# 14DoF_MPU9150.net
KiCad netlist of a schematic drawn in EAGLE
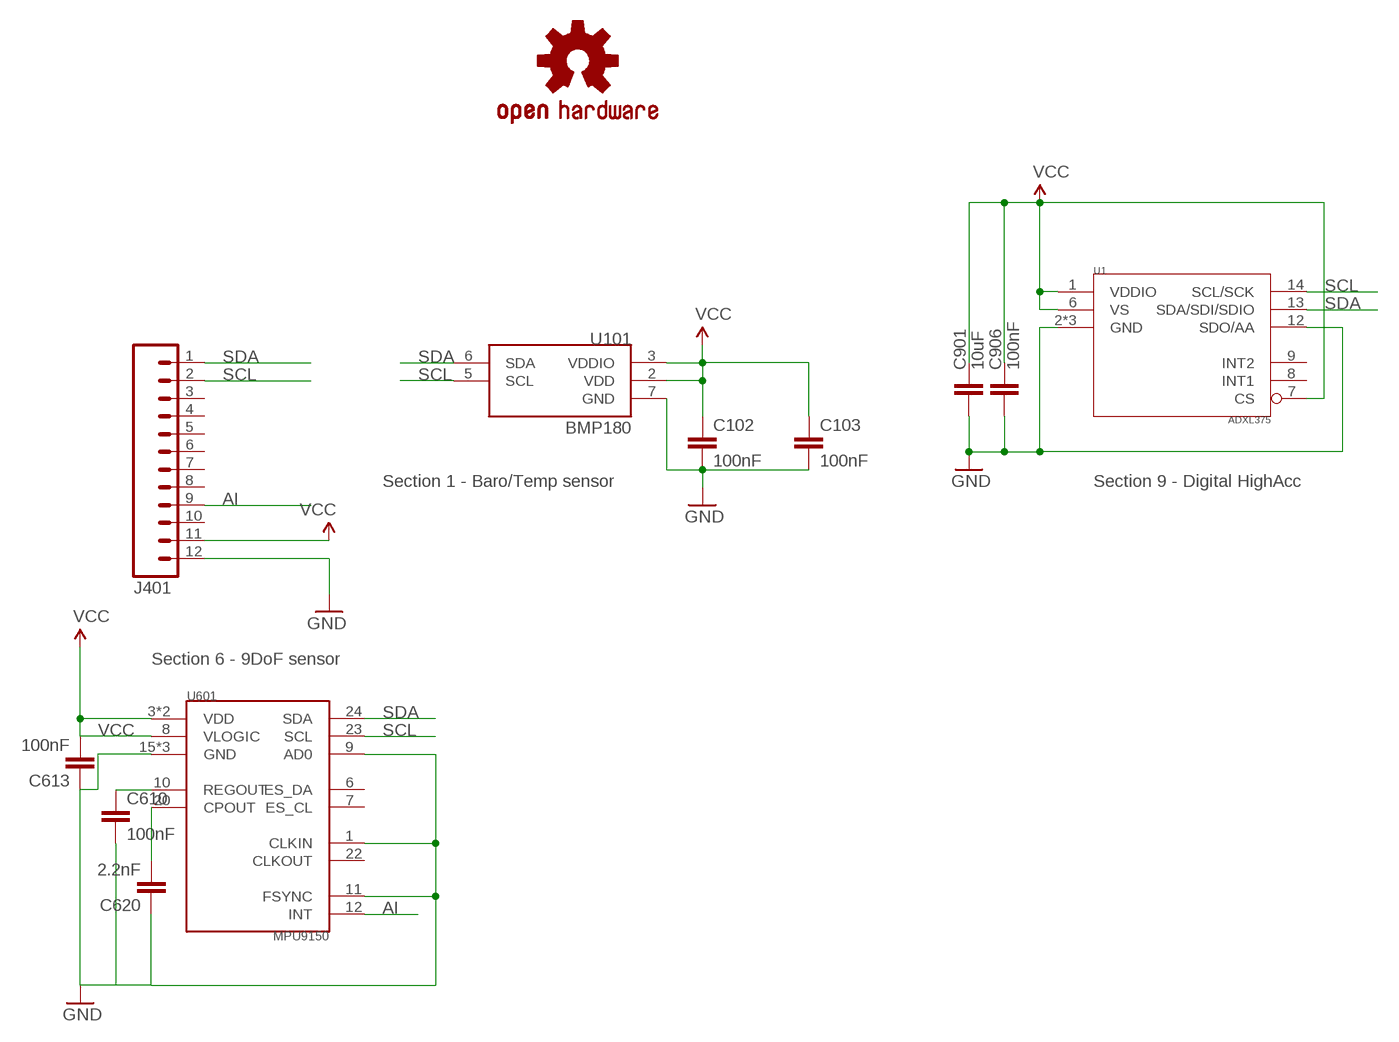
[diagram p0: schematic, sheet 1]

(export (version "E")
  (design (tool "Eeschema 10.0.6"))
  (components
    (comp (ref "C102")
      (value "100nF")
      (footprint "eagle-import:0603-CAP")
      (libsource (lib "eagle-import") (part "CAP0603-CAP"))
    )
    (comp (ref "C103")
      (value "100nF")
      (footprint "eagle-import:0603-CAP")
      (libsource (lib "eagle-import") (part "CAP0603-CAP"))
    )
    (comp (ref "C610")
      (value "100nF")
      (footprint "eagle-import:0603-CAP")
      (libsource (lib "eagle-import") (part "CAP0603-CAP"))
    )
    (comp (ref "C613")
      (value "100nF")
      (footprint "eagle-import:0603-CAP")
      (libsource (lib "eagle-import") (part "CAP0603-CAP"))
    )
    (comp (ref "C620")
      (value "2.2nF")
      (footprint "eagle-import:0603-CAP")
      (libsource (lib "eagle-import") (part "CAP0603-CAP"))
    )
    (comp (ref "C901")
      (value "10uF")
      (footprint "eagle-import:0603-CAP")
      (libsource (lib "eagle-import") (part "CAP0603-CAP"))
    )
    (comp (ref "C906")
      (value "100nF")
      (footprint "eagle-import:0402-CAP")
      (libsource (lib "eagle-import") (part "SparkFun-Passives_CAP0402-CAP"))
    )
    (comp (ref "J401")
      (value "M12PTH")
      (footprint "eagle-import:1X12")
      (libsource (lib "eagle-import") (part "M12PTH"))
    )
    (comp (ref "U$2")
      (value "OSHW-LOGOS")
      (footprint "eagle-import:OSHW-LOGO-S")
      (libsource (lib "eagle-import") (part "OSHW-LOGOS"))
    )
    (comp (ref "U1")
      (value "ADXL375")
      (footprint "eagle-import:ADXL375")
      (libsource (lib "eagle-import") (part "ADXL375"))
    )
    (comp (ref "U101")
      (value "BMP180")
      (footprint "eagle-import:BMP180")
      (libsource (lib "eagle-import") (part "BMP180"))
    )
    (comp (ref "U601")
      (value "MPU9150")
      (footprint "eagle-import:LLGA24")
      (libsource (lib "eagle-import") (part "MPU9150"))
    )
  )
  (nets
    (net (code "1") (name "/AI") (class "Default")
      (node (ref "J401") (pin "9") (pinfunction "9_9") (pintype "passive"))
      (node (ref "U601") (pin "12") (pinfunction "INT_12") (pintype "bidirectional"))
    )
    (net (code "2") (name "/SCL") (class "Default")
      (node (ref "J401") (pin "2") (pinfunction "2_2") (pintype "passive"))
      (node (ref "U1") (pin "14") (pinfunction "SCL/SCK_14") (pintype "input"))
      (node (ref "U101") (pin "5") (pinfunction "SCL_5") (pintype "input"))
      (node (ref "U601") (pin "23") (pinfunction "SCL_23") (pintype "bidirectional"))
    )
    (net (code "3") (name "/SDA") (class "Default")
      (node (ref "J401") (pin "1") (pinfunction "1_1") (pintype "passive"))
      (node (ref "U1") (pin "13") (pinfunction "SDA/SDI/SDIO_13") (pintype "bidirectional"))
      (node (ref "U101") (pin "6") (pinfunction "SDA_6") (pintype "bidirectional"))
      (node (ref "U601") (pin "24") (pinfunction "SDA_24") (pintype "bidirectional"))
    )
    (net (code "4") (name "GND") (class "Default")
      (node (ref "C102") (pin "2") (pinfunction "2_2") (pintype "passive"))
      (node (ref "C103") (pin "2") (pinfunction "2_2") (pintype "passive"))
      (node (ref "C610") (pin "2") (pinfunction "2_2") (pintype "passive"))
      (node (ref "C613") (pin "1") (pinfunction "1_1") (pintype "passive"))
      (node (ref "C620") (pin "1") (pinfunction "1_1") (pintype "passive"))
      (node (ref "C901") (pin "2") (pinfunction "2_2") (pintype "passive"))
      (node (ref "C906") (pin "2") (pinfunction "2_2") (pintype "passive"))
      (node (ref "J401") (pin "12") (pinfunction "12_12") (pintype "passive"))
      (node (ref "U1") (pin "12") (pinfunction "SDO/AA_12") (pintype "bidirectional"))
      (node (ref "U1") (pin "2") (pinfunction "GND_2") (pintype "power_in"))
      (node (ref "U1") (pin "4") (pinfunction "GND_4") (pintype "power_in"))
      (node (ref "U1") (pin "5") (pinfunction "GND_5") (pintype "power_in"))
      (node (ref "U101") (pin "7") (pinfunction "GND_7") (pintype "power_in"))
      (node (ref "U601") (pin "1") (pinfunction "CLKIN_1") (pintype "bidirectional"))
      (node (ref "U601") (pin "11") (pinfunction "FSYNC_11") (pintype "bidirectional"))
      (node (ref "U601") (pin "15") (pinfunction "GND_15") (pintype "bidirectional"))
      (node (ref "U601") (pin "17") (pinfunction "GND_17") (pintype "bidirectional"))
      (node (ref "U601") (pin "18") (pinfunction "GND_18") (pintype "bidirectional"))
      (node (ref "U601") (pin "9") (pinfunction "AD0_9") (pintype "bidirectional"))
    )
    (net (code "5") (name "Net-(U601-CPOUT)") (class "Default")
      (node (ref "C620") (pin "2") (pinfunction "2_2") (pintype "passive"))
      (node (ref "U601") (pin "20") (pinfunction "CPOUT_20") (pintype "bidirectional"))
    )
    (net (code "6") (name "Net-(U601-REGOUT)") (class "Default")
      (node (ref "C610") (pin "1") (pinfunction "1_1") (pintype "passive"))
      (node (ref "U601") (pin "10") (pinfunction "REGOUT_10") (pintype "bidirectional"))
    )
    (net (code "7") (name "VCC") (class "Default")
      (node (ref "C102") (pin "1") (pinfunction "1_1") (pintype "passive"))
      (node (ref "C103") (pin "1") (pinfunction "1_1") (pintype "passive"))
      (node (ref "C613") (pin "2") (pinfunction "2_2") (pintype "passive"))
      (node (ref "C901") (pin "1") (pinfunction "1_1") (pintype "passive"))
      (node (ref "C906") (pin "1") (pinfunction "1_1") (pintype "passive"))
      (node (ref "J401") (pin "11") (pinfunction "11_11") (pintype "passive"))
      (node (ref "U1") (pin "1") (pinfunction "VDDIO_1") (pintype "power_in"))
      (node (ref "U1") (pin "6") (pinfunction "VS_6") (pintype "power_in"))
      (node (ref "U1") (pin "7") (pinfunction "CS_7") (pintype "input"))
      (node (ref "U101") (pin "2") (pinfunction "VDD_2") (pintype "power_in"))
      (node (ref "U101") (pin "3") (pinfunction "VDDIO_3") (pintype "power_in"))
      (node (ref "U601") (pin "13") (pinfunction "VDD_13") (pintype "bidirectional"))
      (node (ref "U601") (pin "3") (pinfunction "VDD_3") (pintype "bidirectional"))
      (node (ref "U601") (pin "8") (pinfunction "VLOGIC_8") (pintype "bidirectional"))
    )
    (net (code "8") (name "unconnected-(J401-Pad3)") (class "Default")
      (node (ref "J401") (pin "3") (pinfunction "3_3") (pintype "passive"))
    )
    (net (code "9") (name "unconnected-(J401-Pad4)") (class "Default")
      (node (ref "J401") (pin "4") (pinfunction "4_4") (pintype "passive"))
    )
    (net (code "10") (name "unconnected-(J401-Pad5)") (class "Default")
      (node (ref "J401") (pin "5") (pinfunction "5_5") (pintype "passive"))
    )
    (net (code "11") (name "unconnected-(J401-Pad6)") (class "Default")
      (node (ref "J401") (pin "6") (pinfunction "6_6") (pintype "passive"))
    )
    (net (code "12") (name "unconnected-(J401-Pad7)") (class "Default")
      (node (ref "J401") (pin "7") (pinfunction "7_7") (pintype "passive"))
    )
    (net (code "13") (name "unconnected-(J401-Pad8)") (class "Default")
      (node (ref "J401") (pin "8") (pinfunction "8_8") (pintype "passive"))
    )
    (net (code "14") (name "unconnected-(J401-Pad10)") (class "Default")
      (node (ref "J401") (pin "10") (pinfunction "10_10") (pintype "passive"))
    )
    (net (code "15") (name "unconnected-(U1-INT1-Pad8)") (class "Default")
      (node (ref "U1") (pin "8") (pinfunction "INT1_8") (pintype "output"))
    )
    (net (code "16") (name "unconnected-(U1-INT2-Pad9)") (class "Default")
      (node (ref "U1") (pin "9") (pinfunction "INT2_9") (pintype "output"))
    )
    (net (code "17") (name "unconnected-(U601-CLKOUT-Pad22)") (class "Default")
      (node (ref "U601") (pin "22") (pinfunction "CLKOUT_22") (pintype "bidirectional"))
    )
    (net (code "18") (name "unconnected-(U601-ES_CL-Pad7)") (class "Default")
      (node (ref "U601") (pin "7") (pinfunction "ES_CL_7") (pintype "bidirectional"))
    )
    (net (code "19") (name "unconnected-(U601-ES_DA-Pad6)") (class "Default")
      (node (ref "U601") (pin "6") (pinfunction "ES_DA_6") (pintype "bidirectional"))
    )
  )
)
